# SB_M12.net
KiCad netlist of a schematic drawn in Altium Designer
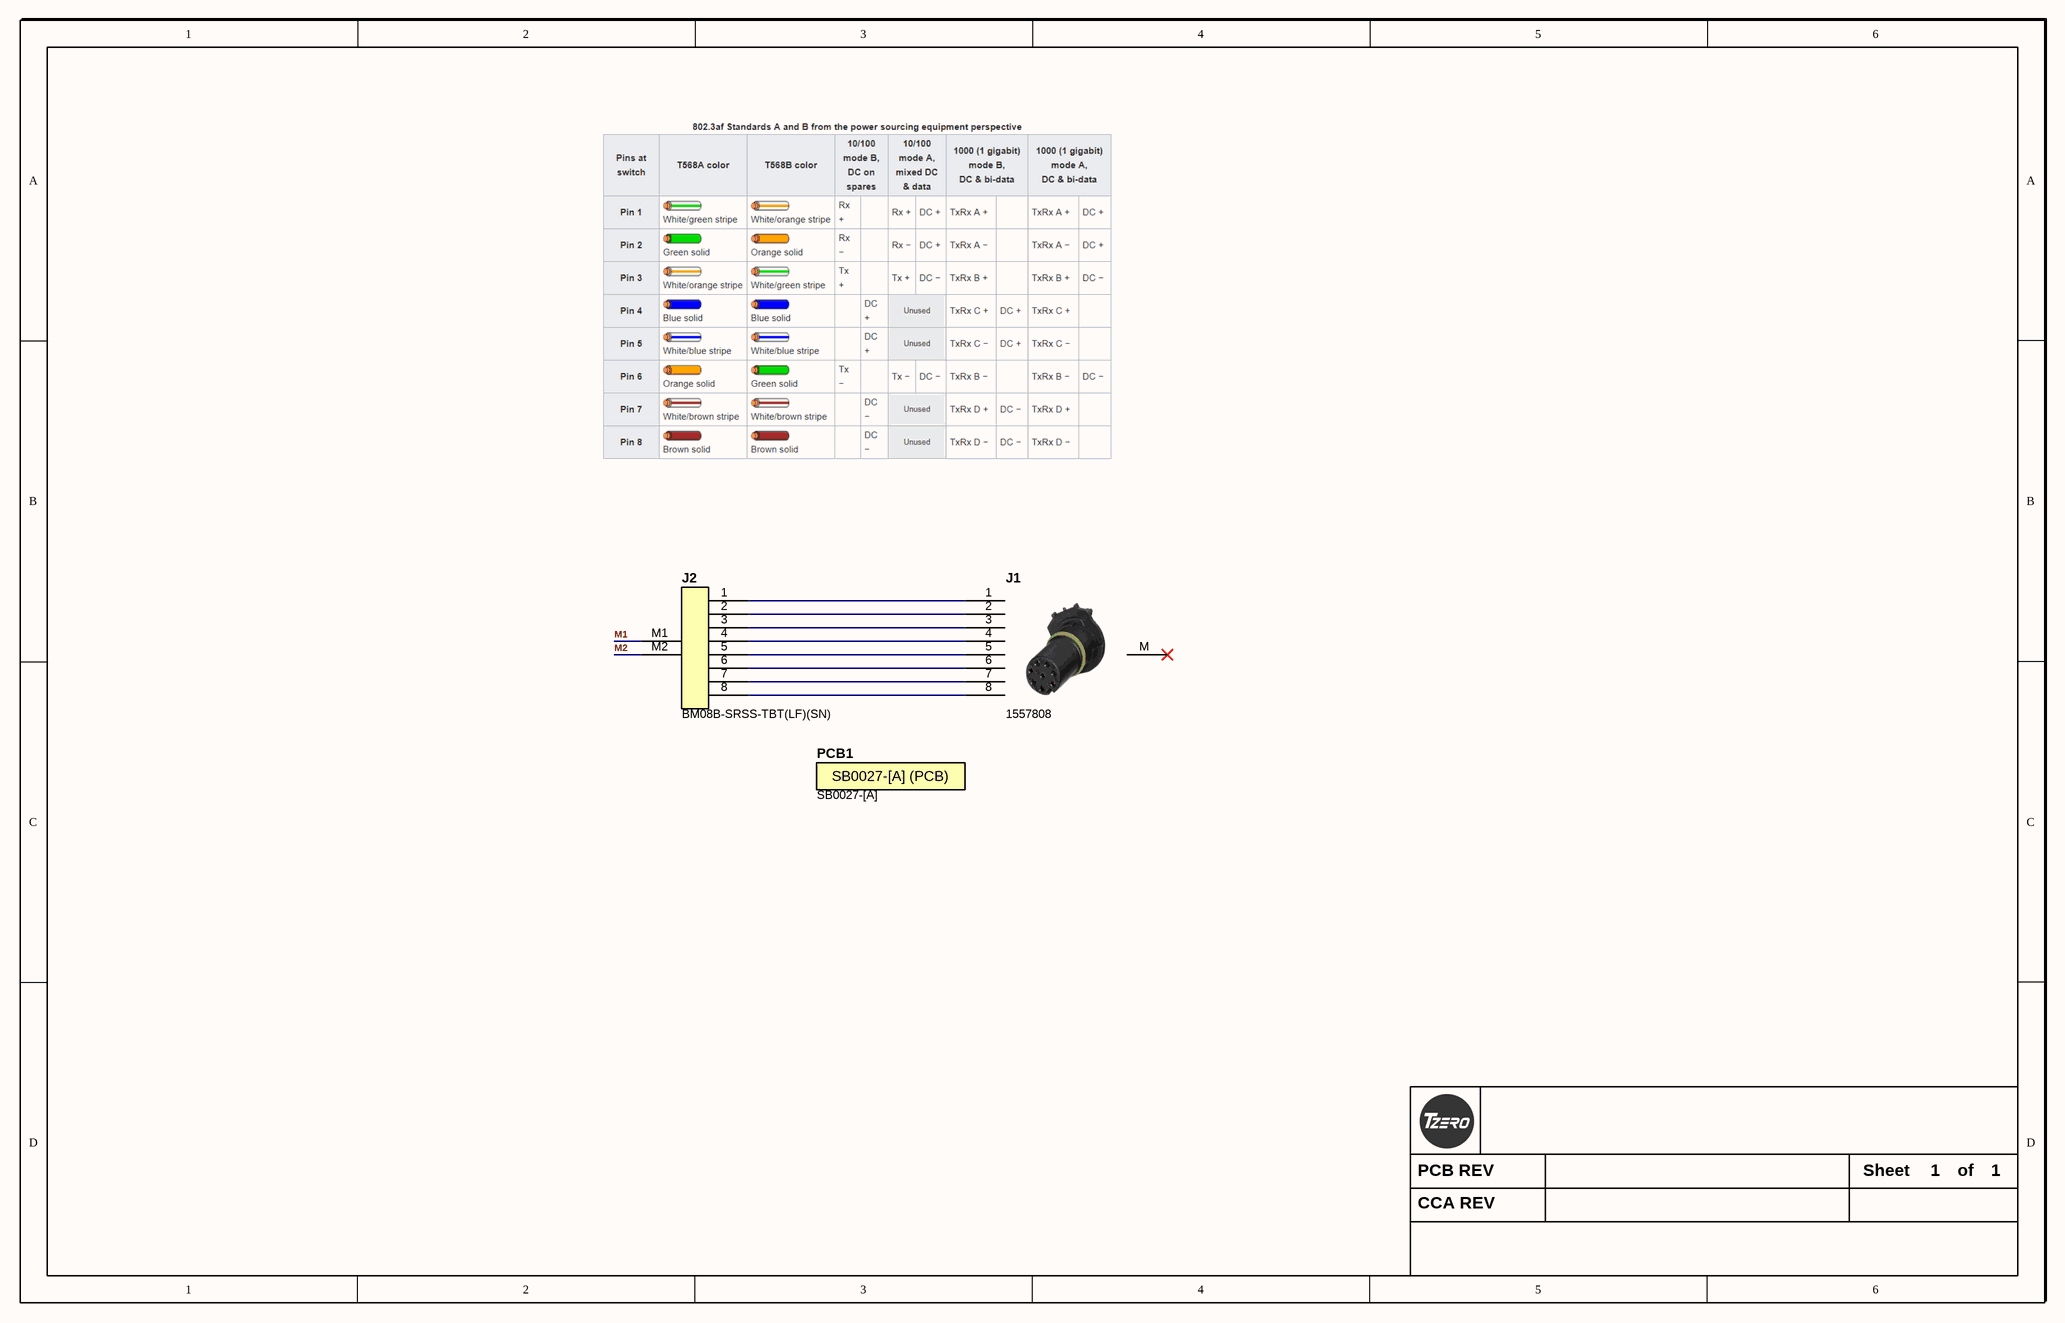
[diagram p0: SB_M12.SchDoc]

(export (version "E")
  (design (tool "Eeschema 10.0.6"))
  (components
    (comp (ref "J1")
      (value "1557808")
      (footprint "1557808")
      (description "Circular Metric Connectors SACC-CI-M12FS -8CON-L180-THR")
      (fields (field (name "MANUFACTURER") "Phoenix Contact"))
      (libsource (lib "eConnector_Phoenix_M12") (part "1557808"))
    )
    (comp (ref "J2")
      (value "BM08B-SRSS-TBT(LF)(SN)")
      (footprint "BM08B-SRSS-TBT(LF)(SN)")
      (description "8 Positions Header, Shrouded Connector 0.039\" (1.00mm) Surface Mount Tin")
      (fields (field (name "MANUFACTURER") "Japan Solderless Terminals (JST)"))
      (libsource (lib "eConnector_JST_SM") (part "BM08B-SRSS-TBT(LF)(SN)"))
    )
    (comp (ref "PCB1")
      (value "SB0027-[A]")
      (description "SB0027 PCB Revision A")
      (fields (field (name "MANUFACTURER") "TZero"))
      (libsource (lib "ePCB") (part "SB0027-[A]"))
    )
  )
  (nets
    (net (code "1") (name "/M1") (class "Default")
      (node (ref "J2") (pin "M1") (pinfunction "M1_M1") (pintype "passive"))
    )
    (net (code "2") (name "/M2") (class "Default")
      (node (ref "J2") (pin "M2") (pinfunction "M2_M2") (pintype "passive"))
    )
    (net (code "3") (name "Net-(J1-Pad1)") (class "Default")
      (node (ref "J1") (pin "1") (pinfunction "1_1") (pintype "passive"))
      (node (ref "J2") (pin "1") (pinfunction "1_1") (pintype "passive"))
    )
    (net (code "4") (name "Net-(J1-Pad2)") (class "Default")
      (node (ref "J1") (pin "2") (pinfunction "2_2") (pintype "passive"))
      (node (ref "J2") (pin "2") (pinfunction "2_2") (pintype "passive"))
    )
    (net (code "5") (name "Net-(J1-Pad3)") (class "Default")
      (node (ref "J1") (pin "3") (pinfunction "3_3") (pintype "passive"))
      (node (ref "J2") (pin "3") (pinfunction "3_3") (pintype "passive"))
    )
    (net (code "6") (name "Net-(J1-Pad4)") (class "Default")
      (node (ref "J1") (pin "4") (pinfunction "4_4") (pintype "passive"))
      (node (ref "J2") (pin "4") (pinfunction "4_4") (pintype "passive"))
    )
    (net (code "7") (name "Net-(J1-Pad5)") (class "Default")
      (node (ref "J1") (pin "5") (pinfunction "5_5") (pintype "passive"))
      (node (ref "J2") (pin "5") (pinfunction "5_5") (pintype "passive"))
    )
    (net (code "8") (name "Net-(J1-Pad6)") (class "Default")
      (node (ref "J1") (pin "6") (pinfunction "6_6") (pintype "passive"))
      (node (ref "J2") (pin "6") (pinfunction "6_6") (pintype "passive"))
    )
    (net (code "9") (name "Net-(J1-Pad7)") (class "Default")
      (node (ref "J1") (pin "7") (pinfunction "7_7") (pintype "passive"))
      (node (ref "J2") (pin "7") (pinfunction "7_7") (pintype "passive"))
    )
    (net (code "10") (name "Net-(J1-Pad8)") (class "Default")
      (node (ref "J1") (pin "8") (pinfunction "8_8") (pintype "passive"))
      (node (ref "J2") (pin "8") (pinfunction "8_8") (pintype "passive"))
    )
    (net (code "11") (name "unconnected-(J1-PadM)") (class "Default")
      (node (ref "J1") (pin "M") (pinfunction "M_M") (pintype "passive+no_connect"))
    )
  )
)
